# Current-LoadSwitches_1V8.net
KiCad netlist of a schematic drawn in Altium Designer
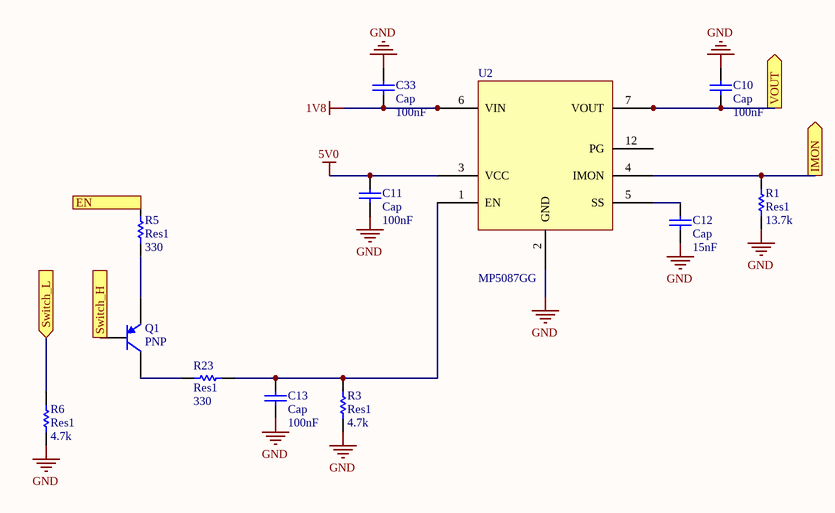
[diagram p0: Current-LoadSwitches 1V8.SchDoc]

(export (version "E")
  (design (tool "Eeschema 10.0.6"))
  (components
    (comp (ref "C10")
      (value "Cap")
      (footprint "0402-A")
      (description "Capacitor")
      (fields (field (name "ALTIUM_VALUE") "100nF") (field (name "PUBLISHER") "Altium Limited"))
      (libsource (lib "Miscellaneous Devices") (part "Cap"))
    )
    (comp (ref "C11")
      (value "Cap")
      (footprint "0402-A")
      (description "Capacitor")
      (fields (field (name "ALTIUM_VALUE") "100nF") (field (name "PUBLISHER") "Altium Limited"))
      (libsource (lib "Miscellaneous Devices") (part "Cap"))
    )
    (comp (ref "C12")
      (value "Cap")
      (footprint "0402-A")
      (description "Capacitor")
      (fields (field (name "ALTIUM_VALUE") "15nF") (field (name "PUBLISHER") "Altium Limited"))
      (libsource (lib "Miscellaneous Devices") (part "Cap"))
    )
    (comp (ref "C13")
      (value "Cap")
      (footprint "0402-A")
      (description "Capacitor")
      (fields (field (name "ALTIUM_VALUE") "100nF") (field (name "PUBLISHER") "Altium Limited"))
      (libsource (lib "Miscellaneous Devices") (part "Cap"))
    )
    (comp (ref "C33")
      (value "Cap")
      (footprint "0402-A")
      (description "Capacitor")
      (fields (field (name "ALTIUM_VALUE") "100nF") (field (name "PUBLISHER") "Altium Limited"))
      (libsource (lib "Miscellaneous Devices") (part "Cap"))
    )
    (comp (ref "Q1")
      (value "PNP")
      (footprint "SOT-23B_N")
      (description "PNP Bipolar Transistor")
      (fields (field (name "PUBLISHER") "Altium Limited"))
      (libsource (lib "Miscellaneous Devices") (part "PNP"))
    )
    (comp (ref "R1")
      (value "Res1")
      (footprint "0402-A")
      (description "Resistor")
      (fields (field (name "ALTIUM_VALUE") "13.7k") (field (name "PUBLISHER") "Altium Limited"))
      (libsource (lib "Miscellaneous Devices") (part "Res1"))
    )
    (comp (ref "R3")
      (value "Res1")
      (footprint "0402-A")
      (description "Resistor")
      (fields (field (name "ALTIUM_VALUE") "4.7k") (field (name "PUBLISHER") "Altium Limited"))
      (libsource (lib "Miscellaneous Devices") (part "Res1"))
    )
    (comp (ref "R5")
      (value "Res1")
      (footprint "0402-A")
      (description "Resistor")
      (fields (field (name "ALTIUM_VALUE") "330") (field (name "PUBLISHER") "Altium Limited"))
      (libsource (lib "Miscellaneous Devices") (part "Res1"))
    )
    (comp (ref "R6")
      (value "Res1")
      (footprint "0402-A")
      (description "Resistor")
      (fields (field (name "ALTIUM_VALUE") "4.7k") (field (name "PUBLISHER") "Altium Limited"))
      (libsource (lib "Miscellaneous Devices") (part "Res1"))
    )
    (comp (ref "R23")
      (value "Res1")
      (footprint "0402-A")
      (description "Resistor")
      (fields (field (name "ALTIUM_VALUE") "330") (field (name "PUBLISHER") "Altium Limited"))
      (libsource (lib "Miscellaneous Devices") (part "Res1"))
    )
    (comp (ref "U2")
      (value "MP5087GG")
      (footprint "MP5087GG-Z")
      (libsource (lib "MP5087GG-Z") (part "Component_1"))
    )
  )
  (nets
    (net (code "1") (name "/EN") (class "Default")
      (node (ref "R5") (pin "2") (pinfunction "2_2") (pintype "passive"))
    )
    (net (code "2") (name "/IMON") (class "Default")
      (node (ref "R1") (pin "2") (pinfunction "2_2") (pintype "passive"))
      (node (ref "U2") (pin "4") (pinfunction "IMON_4") (pintype "passive"))
    )
    (net (code "3") (name "/Switch_H") (class "Default")
      (node (ref "Q1") (pin "2") (pinfunction "B_2") (pintype "passive"))
    )
    (net (code "4") (name "/Switch_L") (class "Default")
      (node (ref "R6") (pin "2") (pinfunction "2_2") (pintype "passive"))
    )
    (net (code "5") (name "/VOUT") (class "Default")
      (node (ref "C10") (pin "1") (pinfunction "1_1") (pintype "passive"))
      (node (ref "U2") (pin "10") (pinfunction "VOUT_10") (pintype "passive"))
      (node (ref "U2") (pin "7") (pinfunction "VOUT_7") (pintype "passive"))
      (node (ref "U2") (pin "8") (pinfunction "VOUT_8") (pintype "passive"))
      (node (ref "U2") (pin "9") (pinfunction "VOUT_9") (pintype "passive"))
    )
    (net (code "6") (name "1V8") (class "Default")
      (node (ref "C33") (pin "1") (pinfunction "1_1") (pintype "passive"))
      (node (ref "U2") (pin "11") (pinfunction "VOUT_11") (pintype "passive"))
      (node (ref "U2") (pin "6") (pinfunction "VIN_6") (pintype "passive"))
    )
    (net (code "7") (name "5V0") (class "Default")
      (node (ref "C11") (pin "2") (pinfunction "2_2") (pintype "passive"))
      (node (ref "U2") (pin "3") (pinfunction "VCC_3") (pintype "passive"))
    )
    (net (code "8") (name "GND") (class "Default")
      (node (ref "C10") (pin "2") (pinfunction "2_2") (pintype "passive"))
      (node (ref "C11") (pin "1") (pinfunction "1_1") (pintype "passive"))
      (node (ref "C12") (pin "1") (pinfunction "1_1") (pintype "passive"))
      (node (ref "C13") (pin "1") (pinfunction "1_1") (pintype "passive"))
      (node (ref "C33") (pin "2") (pinfunction "2_2") (pintype "passive"))
      (node (ref "R1") (pin "1") (pinfunction "1_1") (pintype "passive"))
      (node (ref "R3") (pin "1") (pinfunction "1_1") (pintype "passive"))
      (node (ref "R6") (pin "1") (pinfunction "1_1") (pintype "passive"))
      (node (ref "U2") (pin "2") (pinfunction "GND_2") (pintype "passive"))
    )
    (net (code "9") (name "Net-(Q1-C)") (class "Default")
      (node (ref "Q1") (pin "1") (pinfunction "C_1") (pintype "passive"))
      (node (ref "R23") (pin "1") (pinfunction "1_1") (pintype "passive"))
    )
    (net (code "10") (name "Net-(Q1-E)") (class "Default")
      (node (ref "Q1") (pin "3") (pinfunction "E_3") (pintype "passive"))
      (node (ref "R5") (pin "1") (pinfunction "1_1") (pintype "passive"))
    )
    (net (code "11") (name "Net-(U2-EN)") (class "Default")
      (node (ref "C13") (pin "2") (pinfunction "2_2") (pintype "passive"))
      (node (ref "R23") (pin "2") (pinfunction "2_2") (pintype "passive"))
      (node (ref "R3") (pin "2") (pinfunction "2_2") (pintype "passive"))
      (node (ref "U2") (pin "1") (pinfunction "EN_1") (pintype "passive"))
    )
    (net (code "12") (name "Net-(U2-SS)") (class "Default")
      (node (ref "C12") (pin "2") (pinfunction "2_2") (pintype "passive"))
      (node (ref "U2") (pin "5") (pinfunction "SS_5") (pintype "passive"))
    )
    (net (code "13") (name "unconnected-(U2-PG-Pad12)") (class "Default")
      (node (ref "U2") (pin "12") (pinfunction "PG_12") (pintype "passive"))
    )
  )
)
